# CH32F203RCT6-R0.net
KiCad netlist of a schematic drawn in Altium Designer
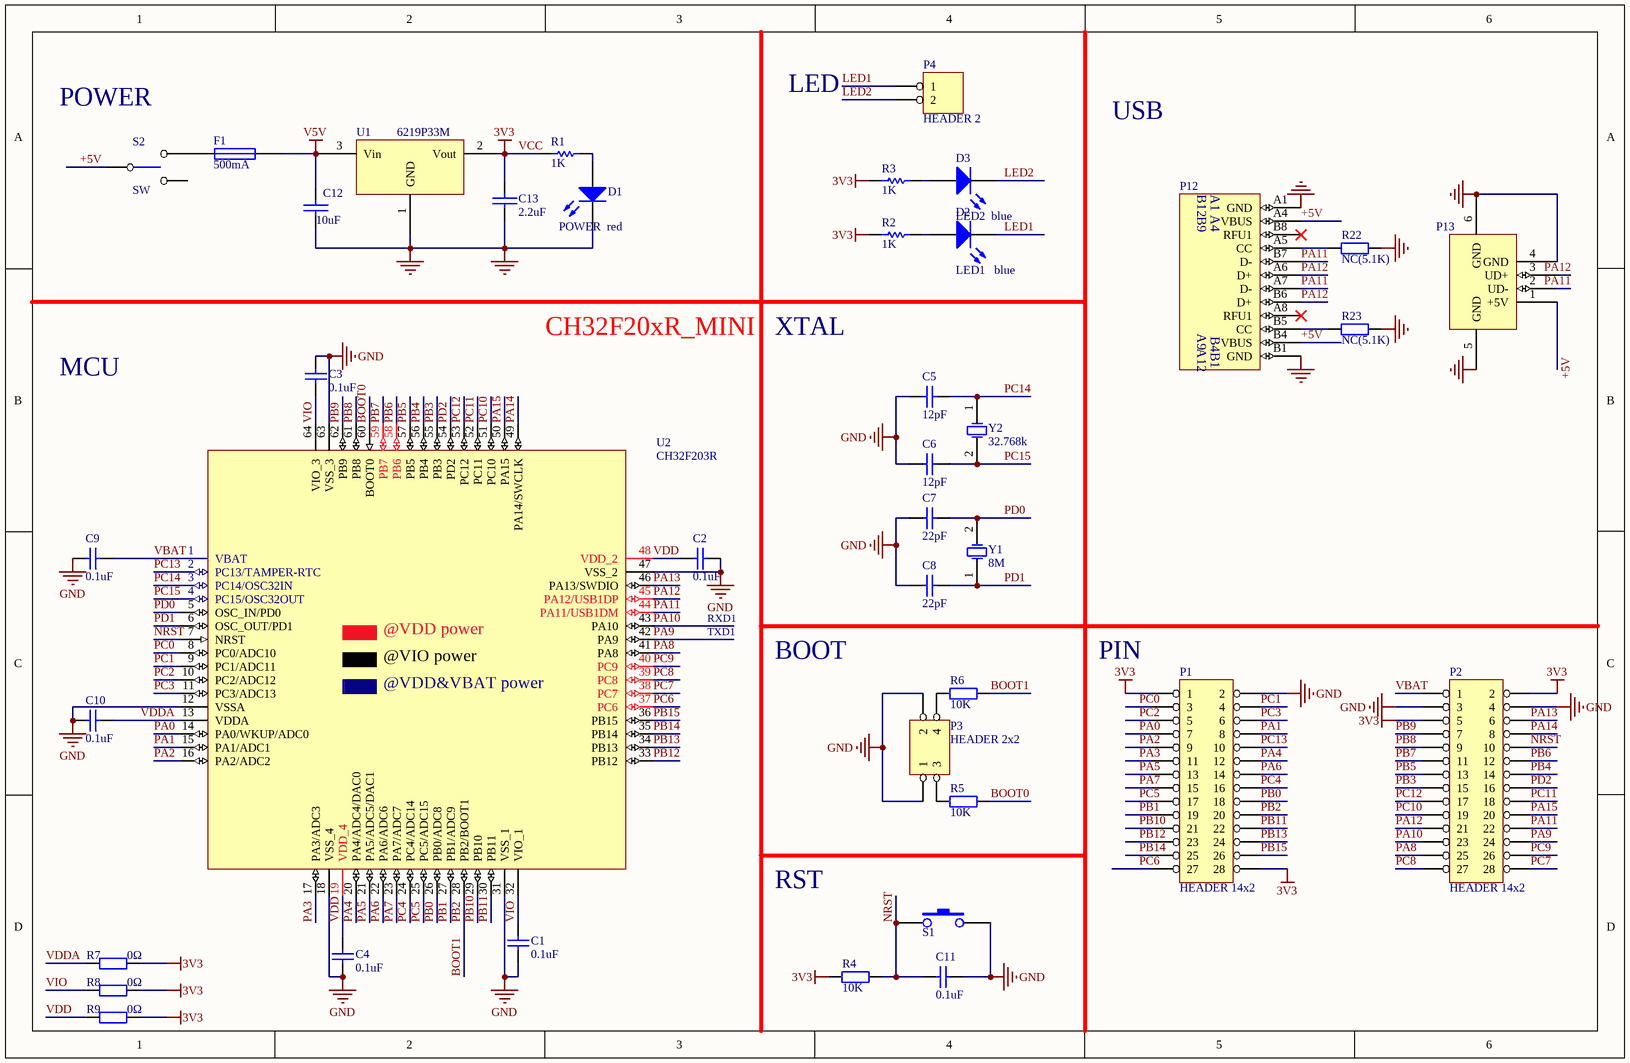
[diagram p0: CH32F203RCT6-R0.SchDoc]

(export (version "E")
  (design (tool "Eeschema 10.0.6"))
  (components
    (comp (ref "C1")
      (value "0.1uF")
      (footprint "0603_C")
      (description "Capacitor")
      (fields (field (name "PUBLISHER") "Altium Limited"))
      (libsource (lib "Miscellaneous Devices") (part "Cap"))
    )
    (comp (ref "C2")
      (value "0.1uF")
      (footprint "0603_C")
      (description "Capacitor")
      (fields (field (name "PUBLISHER") "Altium Limited"))
      (libsource (lib "Miscellaneous Devices") (part "Cap"))
    )
    (comp (ref "C3")
      (value "0.1uF")
      (footprint "0603_C")
      (description "Capacitor")
      (fields (field (name "PUBLISHER") "Altium Limited"))
      (libsource (lib "Miscellaneous Devices") (part "Cap"))
    )
    (comp (ref "C4")
      (value "0.1uF")
      (footprint "0603_C")
      (description "Capacitor")
      (fields (field (name "PUBLISHER") "Altium Limited"))
      (libsource (lib "Miscellaneous Devices") (part "Cap"))
    )
    (comp (ref "C5")
      (value "12pF")
      (footprint "0603_C")
      (description "Capacitor")
      (fields (field (name "PUBLISHER") "Altium Limited"))
      (libsource (lib "Miscellaneous Devices") (part "Cap"))
    )
    (comp (ref "C6")
      (value "12pF")
      (footprint "0603_C")
      (description "Capacitor")
      (fields (field (name "PUBLISHER") "Altium Limited"))
      (libsource (lib "Miscellaneous Devices") (part "Cap"))
    )
    (comp (ref "C7")
      (value "22pF")
      (footprint "0603_C")
      (description "Capacitor")
      (fields (field (name "PUBLISHER") "Altium Limited"))
      (libsource (lib "Miscellaneous Devices") (part "Cap"))
    )
    (comp (ref "C8")
      (value "22pF")
      (footprint "0603_C")
      (description "Capacitor")
      (fields (field (name "PUBLISHER") "Altium Limited"))
      (libsource (lib "Miscellaneous Devices") (part "Cap"))
    )
    (comp (ref "C9")
      (value "0.1uF")
      (footprint "0603_C")
      (description "Capacitor")
      (fields (field (name "PUBLISHER") "Altium Limited"))
      (libsource (lib "Miscellaneous Devices") (part "Cap"))
    )
    (comp (ref "C10")
      (value "0.1uF")
      (footprint "0603_C")
      (description "Capacitor")
      (fields (field (name "PUBLISHER") "Altium Limited"))
      (libsource (lib "Miscellaneous Devices") (part "Cap"))
    )
    (comp (ref "C11")
      (value "0.1uF")
      (footprint "0603_C")
      (description "Capacitor")
      (fields (field (name "PUBLISHER") "Altium Limited"))
      (libsource (lib "Miscellaneous Devices") (part "Cap"))
    )
    (comp (ref "C12")
      (value "10uF")
      (footprint "3216_C")
      (description "Capacitor")
      (libsource (lib "*") (part "CAP"))
    )
    (comp (ref "C13")
      (value "2.2uF")
      (footprint "0603_C")
      (description "Capacitor")
      (libsource (lib "*") (part "CAP"))
    )
    (comp (ref "D1")
      (value "POWER  red")
      (footprint "0603+")
      (description "Typical INFRARED GaAs LED")
      (fields (field (name "PUBLISHER") "Altium Limited"))
      (libsource (lib "Miscellaneous Devices") (part "LED0"))
    )
    (comp (ref "D2")
      (value "LED1   blue")
      (footprint "0603+")
      (description "Typical INFRARED GaAs LED")
      (fields (field (name "PUBLISHER") "Altium Limited"))
      (libsource (lib "Miscellaneous Devices") (part "LED0"))
    )
    (comp (ref "D3")
      (value "LED2  blue")
      (footprint "0603+")
      (description "Typical INFRARED GaAs LED")
      (fields (field (name "PUBLISHER") "Altium Limited"))
      (libsource (lib "Miscellaneous Devices") (part "LED0"))
    )
    (comp (ref "F1")
      (value "500mA")
      (footprint "0603")
      (description "Fuse")
      (libsource (lib "*") (part "FUSE1"))
    )
    (comp (ref "P1")
      (value "HEADER 14x2")
      (footprint "MYPCB:IDC28-2.54MM")
      (description "Header, 14-Pin, Dual row")
      (libsource (lib "wch_sch_others") (part "HEADER 14x2"))
    )
    (comp (ref "P2")
      (value "HEADER 14x2")
      (footprint "MYPCB:IDC28-2.54MM")
      (description "Header, 14-Pin, Dual row")
      (libsource (lib "wch_sch_others") (part "HEADER 14x2"))
    )
    (comp (ref "P3")
      (value "HEADER 2x2")
      (footprint "MYPCB:IDC4-2.54MM")
      (description "Header, 2-Pin, Dual row")
      (libsource (lib "wch_sch_others") (part "HEADER 2x2"))
    )
    (comp (ref "P4")
      (value "HEADER 2")
      (footprint "MYPCB:SIP2-2.54mm")
      (description "Header, 2-Pin")
      (libsource (lib "wch_sch_others") (part "HEADER 2"))
    )
    (comp (ref "P12")
      (value "TYPE-C")
      (footprint "TYPE-C-Receptacle-2.0")
      (libsource (lib "*") (part "TYPE-C1"))
    )
    (comp (ref "P13")
      (value "USB_A")
      (footprint "USBAF")
      (description "USB Port")
      (libsource (lib "CHXXXSCH") (part "USB"))
    )
    (comp (ref "R1")
      (value "1K")
      (footprint "0603")
      (description "Semiconductor Resistor")
      (fields (field (name "PUBLISHER") "Altium Limited"))
      (libsource (lib "Miscellaneous Devices") (part "Res Semi"))
    )
    (comp (ref "R2")
      (value "1K")
      (footprint "0603")
      (description "Semiconductor Resistor")
      (fields (field (name "PUBLISHER") "Altium Limited"))
      (libsource (lib "Miscellaneous Devices") (part "Res Semi"))
    )
    (comp (ref "R3")
      (value "1K")
      (footprint "0603")
      (description "Semiconductor Resistor")
      (fields (field (name "PUBLISHER") "Altium Limited"))
      (libsource (lib "Miscellaneous Devices") (part "Res Semi"))
    )
    (comp (ref "R4")
      (value "10K")
      (footprint "0603")
      (description "Resistor")
      (fields (field (name "PUBLISHER") "Altium Limited"))
      (libsource (lib "Miscellaneous Devices") (part "Res2"))
    )
    (comp (ref "R5")
      (value "10K")
      (footprint "0603")
      (description "Resistor")
      (fields (field (name "PUBLISHER") "Altium Limited"))
      (libsource (lib "Miscellaneous Devices") (part "Res2"))
    )
    (comp (ref "R6")
      (value "10K")
      (footprint "0603")
      (description "Resistor")
      (fields (field (name "PUBLISHER") "Altium Limited"))
      (libsource (lib "Miscellaneous Devices") (part "Res2"))
    )
    (comp (ref "R7")
      (value "0Ω")
      (footprint "0603")
      (description "Resistor")
      (fields (field (name "PUBLISHER") "Altium Limited"))
      (libsource (lib "Miscellaneous Devices") (part "Res2"))
    )
    (comp (ref "R8")
      (value "0Ω")
      (footprint "0603")
      (description "Resistor")
      (fields (field (name "PUBLISHER") "Altium Limited"))
      (libsource (lib "Miscellaneous Devices") (part "Res2"))
    )
    (comp (ref "R9")
      (value "0Ω")
      (footprint "0603")
      (description "Resistor")
      (fields (field (name "PUBLISHER") "Altium Limited"))
      (libsource (lib "Miscellaneous Devices") (part "Res2"))
    )
    (comp (ref "R22")
      (value "NC(5.1K)")
      (footprint "0603")
      (description "Resistor")
      (libsource (lib "") (part "Res2_1"))
    )
    (comp (ref "R23")
      (value "NC(5.1K)")
      (footprint "0603")
      (description "Resistor")
      (libsource (lib "") (part "Res2_1"))
    )
    (comp (ref "S1")
      (value "RST")
      (footprint "SMD_6.1x3.65x2.5mm-KEY")
      (libsource (lib "CCDXPLIB") (part "KEY"))
    )
    (comp (ref "S2") (value "SW") (footprint "KEY2") (libsource (lib "MYSCH") (part "SW")))
    (comp (ref "U1")
      (value "6219P33M")
      (footprint "SOT-23")
      (libsource (lib "wch_sch_others") (part "6219P33M"))
    )
    (comp (ref "U2")
      (value "CH32F203R")
      (footprint "LQFP64M_10x10")
      (description "ARM M3 HD-MCU, 144MHz, 8*UART, 10*Timer, 4*OPA")
      (libsource (lib "CHXXX") (part "CH32F203R"))
    )
    (comp (ref "Y1")
      (value "8M")
      (footprint "XT_AT49")
      (description "Crystal Oscillator")
      (fields (field (name "PUBLISHER") "Altium Limited"))
      (libsource (lib "Miscellaneous Devices") (part "XTAL"))
    )
    (comp (ref "Y2")
      (value "32.768k")
      (footprint "FC-135")
      (description "Crystal Oscillator")
      (fields (field (name "PUBLISHER") "Altium Limited"))
      (libsource (lib "Miscellaneous Devices") (part "XTAL"))
    )
  )
  (nets
    (net (code "1") (name "/+5V") (class "Default")
      (node (ref "P12") (pin "A4") (pinfunction "VBUS_A4") (pintype "bidirectional"))
      (node (ref "P12") (pin "B4") (pinfunction "VBUS_B4") (pintype "bidirectional"))
      (node (ref "P13") (pin "1") (pinfunction "+5V_1") (pintype "power_in"))
      (node (ref "S2") (pin "1") (pinfunction "1_1") (pintype "passive"))
    )
    (net (code "3") (name "/BOOT0") (class "Default")
      (node (ref "R5") (pin "1") (pinfunction "1_1") (pintype "passive"))
      (node (ref "U2") (pin "60") (pinfunction "BOOT0_60") (pintype "input"))
    )
    (net (code "4") (name "/BOOT1") (class "Default")
      (node (ref "P1") (pin "20") (pinfunction "20_20") (pintype "passive"))
      (node (ref "R6") (pin "1") (pinfunction "1_1") (pintype "passive"))
      (node (ref "U2") (pin "28") (pinfunction "PB2/BOOT1_28") (pintype "bidirectional"))
    )
    (net (code "5") (name "/LED1") (class "Default")
      (node (ref "D2") (pin "2") (pinfunction "K_2") (pintype "passive"))
      (node (ref "P4") (pin "1") (pinfunction "1_1") (pintype "passive"))
    )
    (net (code "6") (name "/LED2") (class "Default")
      (node (ref "D3") (pin "2") (pinfunction "K_2") (pintype "passive"))
      (node (ref "P4") (pin "2") (pinfunction "2_2") (pintype "passive"))
    )
    (net (code "7") (name "/NRST") (class "Default")
      (node (ref "C11") (pin "2") (pinfunction "2_2") (pintype "passive"))
      (node (ref "P2") (pin "10") (pinfunction "10_10") (pintype "passive"))
      (node (ref "R4") (pin "1") (pinfunction "1_1") (pintype "passive"))
      (node (ref "S1") (pin "1") (pinfunction "1_1") (pintype "passive"))
      (node (ref "U2") (pin "7") (pinfunction "NRST_7") (pintype "input"))
    )
    (net (code "8") (name "/PA0") (class "Default")
      (node (ref "P1") (pin "7") (pinfunction "7_7") (pintype "passive"))
      (node (ref "U2") (pin "14") (pinfunction "PA0/WKUP/ADC0_14") (pintype "bidirectional"))
    )
    (net (code "9") (name "/PA1") (class "Default")
      (node (ref "P1") (pin "8") (pinfunction "8_8") (pintype "passive"))
      (node (ref "U2") (pin "15") (pinfunction "PA1/ADC1_15") (pintype "bidirectional"))
    )
    (net (code "10") (name "/PA2") (class "Default")
      (node (ref "P1") (pin "9") (pinfunction "9_9") (pintype "passive"))
      (node (ref "U2") (pin "16") (pinfunction "PA2/ADC2_16") (pintype "bidirectional"))
    )
    (net (code "11") (name "/PA3") (class "Default")
      (node (ref "P1") (pin "11") (pinfunction "11_11") (pintype "passive"))
      (node (ref "U2") (pin "17") (pinfunction "PA3/ADC3_17") (pintype "bidirectional"))
    )
    (net (code "12") (name "/PA4") (class "Default")
      (node (ref "P1") (pin "12") (pinfunction "12_12") (pintype "passive"))
      (node (ref "U2") (pin "20") (pinfunction "PA4/ADC4/DAC0_20") (pintype "bidirectional"))
    )
    (net (code "13") (name "/PA5") (class "Default")
      (node (ref "P1") (pin "13") (pinfunction "13_13") (pintype "passive"))
      (node (ref "U2") (pin "21") (pinfunction "PA5/ADC5/DAC1_21") (pintype "bidirectional"))
    )
    (net (code "14") (name "/PA6") (class "Default")
      (node (ref "P1") (pin "14") (pinfunction "14_14") (pintype "passive"))
      (node (ref "U2") (pin "22") (pinfunction "PA6/ADC6_22") (pintype "bidirectional"))
    )
    (net (code "15") (name "/PA7") (class "Default")
      (node (ref "P1") (pin "15") (pinfunction "15_15") (pintype "passive"))
      (node (ref "U2") (pin "23") (pinfunction "PA7/ADC7_23") (pintype "bidirectional"))
    )
    (net (code "16") (name "/PA8") (class "Default")
      (node (ref "P2") (pin "25") (pinfunction "25_25") (pintype "passive"))
      (node (ref "U2") (pin "41") (pinfunction "PA8_41") (pintype "bidirectional"))
    )
    (net (code "17") (name "/PA9") (class "Default")
      (node (ref "P2") (pin "24") (pinfunction "24_24") (pintype "passive"))
      (node (ref "U2") (pin "42") (pinfunction "PA9_42") (pintype "bidirectional"))
    )
    (net (code "18") (name "/PA10") (class "Default")
      (node (ref "P2") (pin "23") (pinfunction "23_23") (pintype "passive"))
      (node (ref "U2") (pin "43") (pinfunction "PA10_43") (pintype "bidirectional"))
    )
    (net (code "19") (name "/PA11") (class "Default")
      (node (ref "P12") (pin "A7") (pinfunction "D-_A7") (pintype "bidirectional"))
      (node (ref "P12") (pin "B7") (pinfunction "D-_B7") (pintype "bidirectional"))
      (node (ref "P2") (pin "22") (pinfunction "22_22") (pintype "passive"))
      (node (ref "U2") (pin "44") (pinfunction "PA11/USB1DM_44") (pintype "bidirectional"))
    )
    (net (code "20") (name "/PA12") (class "Default")
      (node (ref "P12") (pin "A6") (pinfunction "D+_A6") (pintype "bidirectional"))
      (node (ref "P12") (pin "B6") (pinfunction "D+_B6") (pintype "bidirectional"))
      (node (ref "P2") (pin "21") (pinfunction "21_21") (pintype "passive"))
      (node (ref "U2") (pin "45") (pinfunction "PA12/USB1DP_45") (pintype "bidirectional"))
    )
    (net (code "21") (name "/PA13") (class "Default")
      (node (ref "P2") (pin "6") (pinfunction "6_6") (pintype "passive"))
      (node (ref "U2") (pin "46") (pinfunction "PA13/SWDIO_46") (pintype "bidirectional"))
    )
    (net (code "22") (name "/PA14") (class "Default")
      (node (ref "P2") (pin "8") (pinfunction "8_8") (pintype "passive"))
      (node (ref "U2") (pin "49") (pinfunction "PA14/SWCLK_49") (pintype "bidirectional"))
    )
    (net (code "23") (name "/PA15") (class "Default")
      (node (ref "P2") (pin "20") (pinfunction "20_20") (pintype "passive"))
      (node (ref "U2") (pin "50") (pinfunction "PA15_50") (pintype "bidirectional"))
    )
    (net (code "24") (name "/PB0") (class "Default")
      (node (ref "P1") (pin "18") (pinfunction "18_18") (pintype "passive"))
      (node (ref "U2") (pin "26") (pinfunction "PB0/ADC8_26") (pintype "bidirectional"))
    )
    (net (code "25") (name "/PB1") (class "Default")
      (node (ref "P1") (pin "19") (pinfunction "19_19") (pintype "passive"))
      (node (ref "U2") (pin "27") (pinfunction "PB1/ADC9_27") (pintype "bidirectional"))
    )
    (net (code "26") (name "/PB3") (class "Default")
      (node (ref "P2") (pin "15") (pinfunction "15_15") (pintype "passive"))
      (node (ref "U2") (pin "55") (pinfunction "PB3_55") (pintype "bidirectional"))
    )
    (net (code "27") (name "/PB4") (class "Default")
      (node (ref "P2") (pin "14") (pinfunction "14_14") (pintype "passive"))
      (node (ref "U2") (pin "56") (pinfunction "PB4_56") (pintype "bidirectional"))
    )
    (net (code "28") (name "/PB5") (class "Default")
      (node (ref "P2") (pin "13") (pinfunction "13_13") (pintype "passive"))
      (node (ref "U2") (pin "57") (pinfunction "PB5_57") (pintype "bidirectional"))
    )
    (net (code "29") (name "/PB6") (class "Default")
      (node (ref "P2") (pin "12") (pinfunction "12_12") (pintype "passive"))
      (node (ref "U2") (pin "58") (pinfunction "PB6_58") (pintype "bidirectional"))
    )
    (net (code "30") (name "/PB7") (class "Default")
      (node (ref "P2") (pin "11") (pinfunction "11_11") (pintype "passive"))
      (node (ref "U2") (pin "59") (pinfunction "PB7_59") (pintype "bidirectional"))
    )
    (net (code "31") (name "/PB8") (class "Default")
      (node (ref "P2") (pin "9") (pinfunction "9_9") (pintype "passive"))
      (node (ref "U2") (pin "61") (pinfunction "PB8_61") (pintype "bidirectional"))
    )
    (net (code "32") (name "/PB9") (class "Default")
      (node (ref "P2") (pin "7") (pinfunction "7_7") (pintype "passive"))
      (node (ref "U2") (pin "62") (pinfunction "PB9_62") (pintype "bidirectional"))
    )
    (net (code "33") (name "/PB10") (class "Default")
      (node (ref "P1") (pin "21") (pinfunction "21_21") (pintype "passive"))
      (node (ref "U2") (pin "29") (pinfunction "PB10_29") (pintype "bidirectional"))
    )
    (net (code "34") (name "/PB11") (class "Default")
      (node (ref "P1") (pin "22") (pinfunction "22_22") (pintype "passive"))
      (node (ref "U2") (pin "30") (pinfunction "PB11_30") (pintype "bidirectional"))
    )
    (net (code "35") (name "/PB12") (class "Default")
      (node (ref "P1") (pin "23") (pinfunction "23_23") (pintype "passive"))
      (node (ref "U2") (pin "33") (pinfunction "PB12_33") (pintype "bidirectional"))
    )
    (net (code "36") (name "/PB13") (class "Default")
      (node (ref "P1") (pin "24") (pinfunction "24_24") (pintype "passive"))
      (node (ref "U2") (pin "34") (pinfunction "PB13_34") (pintype "bidirectional"))
    )
    (net (code "37") (name "/PB14") (class "Default")
      (node (ref "P1") (pin "25") (pinfunction "25_25") (pintype "passive"))
      (node (ref "U2") (pin "35") (pinfunction "PB14_35") (pintype "bidirectional"))
    )
    (net (code "38") (name "/PB15") (class "Default")
      (node (ref "P1") (pin "26") (pinfunction "26_26") (pintype "passive"))
      (node (ref "U2") (pin "36") (pinfunction "PB15_36") (pintype "bidirectional"))
    )
    (net (code "39") (name "/PC0") (class "Default")
      (node (ref "P1") (pin "3") (pinfunction "3_3") (pintype "passive"))
      (node (ref "U2") (pin "8") (pinfunction "PC0/ADC10_8") (pintype "bidirectional"))
    )
    (net (code "40") (name "/PC1") (class "Default")
      (node (ref "P1") (pin "4") (pinfunction "4_4") (pintype "passive"))
      (node (ref "U2") (pin "9") (pinfunction "PC1/ADC11_9") (pintype "bidirectional"))
    )
    (net (code "41") (name "/PC2") (class "Default")
      (node (ref "P1") (pin "5") (pinfunction "5_5") (pintype "passive"))
      (node (ref "U2") (pin "10") (pinfunction "PC2/ADC12_10") (pintype "bidirectional"))
    )
    (net (code "42") (name "/PC3") (class "Default")
      (node (ref "P1") (pin "6") (pinfunction "6_6") (pintype "passive"))
      (node (ref "U2") (pin "11") (pinfunction "PC3/ADC13_11") (pintype "bidirectional"))
    )
    (net (code "43") (name "/PC4") (class "Default")
      (node (ref "P1") (pin "16") (pinfunction "16_16") (pintype "passive"))
      (node (ref "U2") (pin "24") (pinfunction "PC4/ADC14_24") (pintype "bidirectional"))
    )
    (net (code "44") (name "/PC5") (class "Default")
      (node (ref "P1") (pin "17") (pinfunction "17_17") (pintype "passive"))
      (node (ref "U2") (pin "25") (pinfunction "PC5/ADC15_25") (pintype "bidirectional"))
    )
    (net (code "45") (name "/PC6") (class "Default")
      (node (ref "P1") (pin "27") (pinfunction "27_27") (pintype "passive"))
      (node (ref "U2") (pin "37") (pinfunction "PC6_37") (pintype "bidirectional"))
    )
    (net (code "46") (name "/PC7") (class "Default")
      (node (ref "P2") (pin "28") (pinfunction "28_28") (pintype "passive"))
      (node (ref "U2") (pin "38") (pinfunction "PC7_38") (pintype "bidirectional"))
    )
    (net (code "47") (name "/PC8") (class "Default")
      (node (ref "P2") (pin "27") (pinfunction "27_27") (pintype "passive"))
      (node (ref "U2") (pin "39") (pinfunction "PC8_39") (pintype "bidirectional"))
    )
    (net (code "48") (name "/PC9") (class "Default")
      (node (ref "P2") (pin "26") (pinfunction "26_26") (pintype "passive"))
      (node (ref "U2") (pin "40") (pinfunction "PC9_40") (pintype "bidirectional"))
    )
    (net (code "49") (name "/PC10") (class "Default")
      (node (ref "P2") (pin "19") (pinfunction "19_19") (pintype "passive"))
      (node (ref "U2") (pin "51") (pinfunction "PC10_51") (pintype "bidirectional"))
    )
    (net (code "50") (name "/PC11") (class "Default")
      (node (ref "P2") (pin "18") (pinfunction "18_18") (pintype "passive"))
      (node (ref "U2") (pin "52") (pinfunction "PC11_52") (pintype "bidirectional"))
    )
    (net (code "51") (name "/PC12") (class "Default")
      (node (ref "P2") (pin "17") (pinfunction "17_17") (pintype "passive"))
      (node (ref "U2") (pin "53") (pinfunction "PC12_53") (pintype "bidirectional"))
    )
    (net (code "52") (name "/PC13") (class "Default")
      (node (ref "P1") (pin "10") (pinfunction "10_10") (pintype "passive"))
      (node (ref "U2") (pin "2") (pinfunction "PC13/TAMPER-RTC_2") (pintype "bidirectional"))
    )
    (net (code "53") (name "/PC14") (class "Default")
      (node (ref "C5") (pin "1") (pinfunction "1_1") (pintype "passive"))
      (node (ref "U2") (pin "3") (pinfunction "PC14/OSC32IN_3") (pintype "bidirectional"))
      (node (ref "Y2") (pin "1") (pinfunction "OSC1_1") (pintype "passive"))
    )
    (net (code "54") (name "/PC15") (class "Default")
      (node (ref "C6") (pin "1") (pinfunction "1_1") (pintype "passive"))
      (node (ref "U2") (pin "4") (pinfunction "PC15/OSC32OUT_4") (pintype "bidirectional"))
      (node (ref "Y2") (pin "2") (pinfunction "OSC2_2") (pintype "passive"))
    )
    (net (code "55") (name "/PD0") (class "Default")
      (node (ref "C7") (pin "2") (pinfunction "2_2") (pintype "passive"))
      (node (ref "U2") (pin "5") (pinfunction "OSC_IN/PD0_5") (pintype "bidirectional"))
      (node (ref "Y1") (pin "2") (pinfunction "OSC2_2") (pintype "passive"))
    )
    (net (code "56") (name "/PD1") (class "Default")
      (node (ref "C8") (pin "2") (pinfunction "2_2") (pintype "passive"))
      (node (ref "U2") (pin "6") (pinfunction "OSC_OUT/PD1_6") (pintype "bidirectional"))
      (node (ref "Y1") (pin "1") (pinfunction "OSC1_1") (pintype "passive"))
    )
    (net (code "57") (name "/PD2") (class "Default")
      (node (ref "P2") (pin "16") (pinfunction "16_16") (pintype "passive"))
      (node (ref "U2") (pin "54") (pinfunction "PD2_54") (pintype "bidirectional"))
    )
    (net (code "58") (name "/VBAT") (class "Default")
      (node (ref "C9") (pin "1") (pinfunction "1_1") (pintype "passive"))
      (node (ref "P2") (pin "1") (pinfunction "1_1") (pintype "passive"))
      (node (ref "U2") (pin "1") (pinfunction "VBAT_1") (pintype "power_in"))
    )
    (net (code "59") (name "/VDD") (class "Default")
      (node (ref "C2") (pin "2") (pinfunction "2_2") (pintype "passive"))
      (node (ref "C4") (pin "2") (pinfunction "2_2") (pintype "passive"))
      (node (ref "R9") (pin "2") (pinfunction "2_2") (pintype "passive"))
      (node (ref "U2") (pin "19") (pinfunction "VDD_4_19") (pintype "power_in"))
      (node (ref "U2") (pin "48") (pinfunction "VDD_2_48") (pintype "power_in"))
    )
    (net (code "60") (name "/VDDA") (class "Default")
      (node (ref "C10") (pin "1") (pinfunction "1_1") (pintype "passive"))
      (node (ref "R7") (pin "2") (pinfunction "2_2") (pintype "passive"))
      (node (ref "U2") (pin "13") (pinfunction "VDDA_13") (pintype "power_in"))
    )
    (net (code "61") (name "/VIO") (class "Default")
      (node (ref "C1") (pin "2") (pinfunction "2_2") (pintype "passive"))
      (node (ref "C3") (pin "2") (pinfunction "2_2") (pintype "passive"))
      (node (ref "R8") (pin "2") (pinfunction "2_2") (pintype "passive"))
      (node (ref "U2") (pin "32") (pinfunction "VIO_1_32") (pintype "power_in"))
      (node (ref "U2") (pin "64") (pinfunction "VIO_3_64") (pintype "power_in"))
    )
    (net (code "62") (name "3V3") (class "Default")
      (node (ref "C13") (pin "1") (pinfunction "1_1") (pintype "passive"))
      (node (ref "P1") (pin "1") (pinfunction "1_1") (pintype "passive"))
      (node (ref "P1") (pin "28") (pinfunction "28_28") (pintype "passive"))
      (node (ref "P2") (pin "2") (pinfunction "2_2") (pintype "passive"))
      (node (ref "P2") (pin "5") (pinfunction "5_5") (pintype "passive"))
      (node (ref "R1") (pin "2") (pinfunction "2_2") (pintype "passive"))
      (node (ref "R2") (pin "1") (pinfunction "1_1") (pintype "passive"))
      (node (ref "R3") (pin "1") (pinfunction "1_1") (pintype "passive"))
      (node (ref "R4") (pin "2") (pinfunction "2_2") (pintype "passive"))
      (node (ref "R7") (pin "1") (pinfunction "1_1") (pintype "passive"))
      (node (ref "R8") (pin "1") (pinfunction "1_1") (pintype "passive"))
      (node (ref "R9") (pin "1") (pinfunction "1_1") (pintype "passive"))
      (node (ref "U1") (pin "2") (pinfunction "Vout_2") (pintype "passive"))
    )
    (net (code "63") (name "GND") (class "Default")
      (node (ref "C1") (pin "1") (pinfunction "1_1") (pintype "passive"))
      (node (ref "C10") (pin "2") (pinfunction "2_2") (pintype "passive"))
      (node (ref "C11") (pin "1") (pinfunction "1_1") (pintype "passive"))
      (node (ref "C12") (pin "2") (pinfunction "2_2") (pintype "passive"))
      (node (ref "C13") (pin "2") (pinfunction "2_2") (pintype "passive"))
      (node (ref "C2") (pin "1") (pinfunction "1_1") (pintype "passive"))
      (node (ref "C3") (pin "1") (pinfunction "1_1") (pintype "passive"))
      (node (ref "C4") (pin "1") (pinfunction "1_1") (pintype "passive"))
      (node (ref "C5") (pin "2") (pinfunction "2_2") (pintype "passive"))
      (node (ref "C6") (pin "2") (pinfunction "2_2") (pintype "passive"))
      (node (ref "C7") (pin "1") (pinfunction "1_1") (pintype "passive"))
      (node (ref "C8") (pin "1") (pinfunction "1_1") (pintype "passive"))
      (node (ref "C9") (pin "2") (pinfunction "2_2") (pintype "passive"))
      (node (ref "D1") (pin "2") (pinfunction "K_2") (pintype "passive"))
      (node (ref "P1") (pin "2") (pinfunction "2_2") (pintype "passive"))
      (node (ref "P12") (pin "A1") (pinfunction "GND_A1") (pintype "bidirectional"))
      (node (ref "P12") (pin "B1") (pinfunction "GND_B1") (pintype "bidirectional"))
      (node (ref "P13") (pin "4") (pinfunction "GND_4") (pintype "power_in"))
      (node (ref "P13") (pin "5") (pinfunction "GND_5") (pintype "power_in"))
      (node (ref "P13") (pin "6") (pinfunction "GND_6") (pintype "power_in"))
      (node (ref "P2") (pin "3") (pinfunction "3_3") (pintype "passive"))
      (node (ref "P2") (pin "4") (pinfunction "4_4") (pintype "passive"))
      (node (ref "P3") (pin "1") (pinfunction "1_1") (pintype "passive"))
      (node (ref "P3") (pin "2") (pinfunction "2_2") (pintype "passive"))
      (node (ref "R22") (pin "2") (pinfunction "2_2") (pintype "passive"))
      (node (ref "R23") (pin "2") (pinfunction "2_2") (pintype "passive"))
      (node (ref "S1") (pin "2") (pinfunction "2_2") (pintype "passive"))
      (node (ref "U1") (pin "1") (pinfunction "GND_1") (pintype "passive"))
      (node (ref "U2") (pin "12") (pinfunction "VSSA_12") (pintype "power_in"))
      (node (ref "U2") (pin "18") (pinfunction "VSS_4_18") (pintype "power_in"))
      (node (ref "U2") (pin "31") (pinfunction "VSS_1_31") (pintype "power_in"))
      (node (ref "U2") (pin "47") (pinfunction "VSS_2_47") (pintype "power_in"))
      (node (ref "U2") (pin "63") (pinfunction "VSS_3_63") (pintype "power_in"))
    )
    (net (code "64") (name "Net-(D1-A)") (class "Default")
      (node (ref "D1") (pin "1") (pinfunction "A_1") (pintype "passive"))
      (node (ref "R1") (pin "1") (pinfunction "1_1") (pintype "passive"))
    )
    (net (code "65") (name "Net-(D2-A)") (class "Default")
      (node (ref "D2") (pin "1") (pinfunction "A_1") (pintype "passive"))
      (node (ref "R2") (pin "2") (pinfunction "2_2") (pintype "passive"))
    )
    (net (code "66") (name "Net-(D3-A)") (class "Default")
      (node (ref "D3") (pin "1") (pinfunction "A_1") (pintype "passive"))
      (node (ref "R3") (pin "2") (pinfunction "2_2") (pintype "passive"))
    )
    (net (code "67") (name "Net-(F1-Pad1)") (class "Default")
      (node (ref "F1") (pin "1") (pinfunction "1_1") (pintype "passive"))
      (node (ref "S2") (pin "3") (pinfunction "3_3") (pintype "passive"))
    )
    (net (code "68") (name "Net-(P3-Pad3)") (class "Default")
      (node (ref "P3") (pin "3") (pinfunction "3_3") (pintype "passive"))
      (node (ref "R5") (pin "2") (pinfunction "2_2") (pintype "passive"))
    )
    (net (code "69") (name "Net-(P3-Pad4)") (class "Default")
      (node (ref "P3") (pin "4") (pinfunction "4_4") (pintype "passive"))
      (node (ref "R6") (pin "2") (pinfunction "2_2") (pintype "passive"))
    )
    (net (code "70") (name "Net-(P12-CC-PadA5)") (class "Default")
      (node (ref "P12") (pin "A5") (pinfunction "CC_A5") (pintype "bidirectional"))
      (node (ref "R22") (pin "1") (pinfunction "1_1") (pintype "passive"))
    )
    (net (code "71") (name "Net-(P12-CC-PadB5)") (class "Default")
      (node (ref "P12") (pin "B5") (pinfunction "CC_B5") (pintype "bidirectional"))
      (node (ref "R23") (pin "1") (pinfunction "1_1") (pintype "passive"))
    )
    (net (code "72") (name "V5V") (class "Default")
      (node (ref "C12") (pin "1") (pinfunction "1_1") (pintype "passive"))
      (node (ref "F1") (pin "2") (pinfunction "2_2") (pintype "passive"))
      (node (ref "U1") (pin "3") (pinfunction "Vin_3") (pintype "passive"))
    )
    (net (code "73") (name "unconnected-(P12-RFU1-PadA8)") (class "Default")
      (node (ref "P12") (pin "A8") (pinfunction "RFU1_A8") (pintype "bidirectional+no_connect"))
    )
    (net (code "74") (name "unconnected-(P12-RFU1-PadB8)") (class "Default")
      (node (ref "P12") (pin "B8") (pinfunction "RFU1_B8") (pintype "bidirectional+no_connect"))
    )
    (net (code "75") (name "unconnected-(P13-UD+-Pad3)") (class "Default")
      (node (ref "P13") (pin "3") (pinfunction "UD+_3") (pintype "bidirectional"))
    )
    (net (code "76") (name "unconnected-(P13-UD--Pad2)") (class "Default")
      (node (ref "P13") (pin "2") (pinfunction "UD-_2") (pintype "bidirectional"))
    )
    (net (code "77") (name "unconnected-(S2-Pad2)") (class "Default")
      (node (ref "S2") (pin "2") (pinfunction "2_2") (pintype "passive"))
    )
  )
)
